# BLUETOOTH_UNIT.net
KiCad netlist of a schematic drawn in Altium Designer
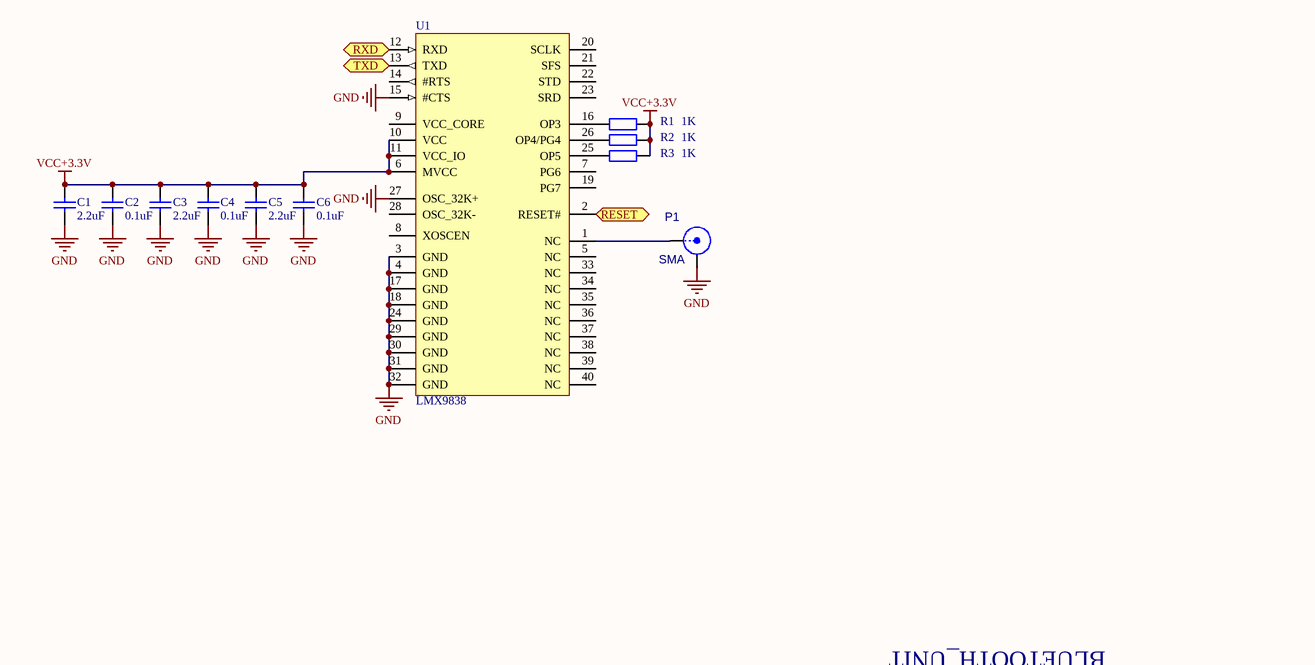
[diagram p0: BLUETOOTH_UNIT.SchDoc]

(export (version "E")
  (design (tool "Eeschema 10.0.6"))
  (components
    (comp (ref "C1")
      (value "2.2uF")
      (footprint "C0603")
      (description "Capasitor_SMD_0808/")
      (fields (field (name "Comment") "0805"))
      (libsource (lib "NEW") (part "Capasitor_SMD_0805"))
    )
    (comp (ref "C2")
      (value "0.1uF")
      (footprint "C0603")
      (description "Capasitor_SMD_0808/")
      (fields (field (name "Comment") "0805"))
      (libsource (lib "NEW") (part "Capasitor_SMD_0805"))
    )
    (comp (ref "C3")
      (value "2.2uF")
      (footprint "C0603")
      (description "Capasitor_SMD_0808/")
      (fields (field (name "Comment") "0805"))
      (libsource (lib "NEW") (part "Capasitor_SMD_0805"))
    )
    (comp (ref "C4")
      (value "0.1uF")
      (footprint "C0603")
      (description "Capasitor_SMD_0808/")
      (fields (field (name "Comment") "0805"))
      (libsource (lib "NEW") (part "Capasitor_SMD_0805"))
    )
    (comp (ref "C5")
      (value "2.2uF")
      (footprint "C0603")
      (description "Capasitor_SMD_0808/")
      (fields (field (name "Comment") "0805"))
      (libsource (lib "NEW") (part "Capasitor_SMD_0805"))
    )
    (comp (ref "C6")
      (value "0.1uF")
      (footprint "C0603")
      (description "Capasitor_SMD_0808/")
      (fields (field (name "Comment") "0805"))
      (libsource (lib "NEW") (part "Capasitor_SMD_0805"))
    )
    (comp (ref "P1")
      (value "SMA")
      (footprint "SMA")
      (fields (field (name "PUBLISHER") "Altium Limited"))
      (libsource (lib "NEW") (part "SMA"))
    )
    (comp (ref "R1")
      (value "1K")
      (footprint "C0603")
      (description "Resistor")
      (fields (field (name "Comment") "RES"))
      (libsource (lib "NEW") (part "RES"))
    )
    (comp (ref "R2")
      (value "1K")
      (footprint "C0603")
      (description "Resistor")
      (fields (field (name "Comment") "RES"))
      (libsource (lib "NEW") (part "RES"))
    )
    (comp (ref "R3")
      (value "1K")
      (footprint "C0603")
      (description "Resistor")
      (fields (field (name "Comment") "RES"))
      (libsource (lib "NEW") (part "RES"))
    )
    (comp (ref "U1")
      (value "LMX9838")
      (footprint "LMX9838")
      (description "Bluetooth module")
      (libsource (lib "NEW") (part "LMX9838"))
    )
  )
  (nets
    (net (code "1") (name "/RESET") (class "Default")
      (node (ref "U1") (pin "2") (pinfunction "RESET#_2") (pintype "passive"))
    )
    (net (code "2") (name "/RXD") (class "Default")
      (node (ref "U1") (pin "12") (pinfunction "RXD_12") (pintype "input"))
    )
    (net (code "3") (name "/TXD") (class "Default")
      (node (ref "U1") (pin "13") (pinfunction "TXD_13") (pintype "output"))
    )
    (net (code "4") (name "GND") (class "Default")
      (node (ref "C1") (pin "2") (pinfunction "2_2") (pintype "passive"))
      (node (ref "C2") (pin "2") (pinfunction "2_2") (pintype "passive"))
      (node (ref "C3") (pin "2") (pinfunction "2_2") (pintype "passive"))
      (node (ref "C4") (pin "2") (pinfunction "2_2") (pintype "passive"))
      (node (ref "C5") (pin "2") (pinfunction "2_2") (pintype "passive"))
      (node (ref "C6") (pin "2") (pinfunction "2_2") (pintype "passive"))
      (node (ref "P1") (pin "2") (pinfunction "Y_2") (pintype "passive"))
      (node (ref "U1") (pin "15") (pinfunction "#CTS_15") (pintype "input"))
      (node (ref "U1") (pin "17") (pinfunction "GND_17") (pintype "passive"))
      (node (ref "U1") (pin "18") (pinfunction "GND_18") (pintype "passive"))
      (node (ref "U1") (pin "24") (pinfunction "GND_24") (pintype "passive"))
      (node (ref "U1") (pin "27") (pinfunction "OSC_32K+_27") (pintype "passive"))
      (node (ref "U1") (pin "29") (pinfunction "GND_29") (pintype "passive"))
      (node (ref "U1") (pin "3") (pinfunction "GND_3") (pintype "passive"))
      (node (ref "U1") (pin "30") (pinfunction "GND_30") (pintype "passive"))
      (node (ref "U1") (pin "31") (pinfunction "GND_31") (pintype "passive"))
      (node (ref "U1") (pin "32") (pinfunction "GND_32") (pintype "passive"))
      (node (ref "U1") (pin "4") (pinfunction "GND_4") (pintype "passive"))
    )
    (net (code "5") (name "Net-(P1-X)") (class "Default")
      (node (ref "P1") (pin "1") (pinfunction "X_1") (pintype "passive"))
      (node (ref "U1") (pin "1") (pinfunction "NC_1") (pintype "passive"))
    )
    (net (code "6") (name "Net-(U1-OP3)") (class "Default")
      (node (ref "R1") (pin "1") (pinfunction "1_1") (pintype "passive"))
      (node (ref "U1") (pin "16") (pinfunction "OP3_16") (pintype "passive"))
    )
    (net (code "7") (name "Net-(U1-OP4{slash}PG4)") (class "Default")
      (node (ref "R2") (pin "1") (pinfunction "1_1") (pintype "passive"))
      (node (ref "U1") (pin "26") (pinfunction "OP4/PG4_26") (pintype "passive"))
    )
    (net (code "8") (name "Net-(U1-OP5)") (class "Default")
      (node (ref "R3") (pin "1") (pinfunction "1_1") (pintype "passive"))
      (node (ref "U1") (pin "25") (pinfunction "OP5_25") (pintype "passive"))
    )
    (net (code "9") (name "VCC+3.3V") (class "Default")
      (node (ref "C1") (pin "1") (pinfunction "1_1") (pintype "passive"))
      (node (ref "C2") (pin "1") (pinfunction "1_1") (pintype "passive"))
      (node (ref "C3") (pin "1") (pinfunction "1_1") (pintype "passive"))
      (node (ref "C4") (pin "1") (pinfunction "1_1") (pintype "passive"))
      (node (ref "C5") (pin "1") (pinfunction "1_1") (pintype "passive"))
      (node (ref "C6") (pin "1") (pinfunction "1_1") (pintype "passive"))
      (node (ref "R1") (pin "2") (pinfunction "2_2") (pintype "passive"))
      (node (ref "R2") (pin "2") (pinfunction "2_2") (pintype "passive"))
      (node (ref "R3") (pin "2") (pinfunction "2_2") (pintype "passive"))
      (node (ref "U1") (pin "10") (pinfunction "VCC_10") (pintype "passive"))
      (node (ref "U1") (pin "11") (pinfunction "VCC_IO_11") (pintype "passive"))
      (node (ref "U1") (pin "6") (pinfunction "MVCC_6") (pintype "passive"))
    )
    (net (code "10") (name "unconnected-(U1-#RTS-Pad14)") (class "Default")
      (node (ref "U1") (pin "14") (pinfunction "#RTS_14") (pintype "output"))
    )
    (net (code "11") (name "unconnected-(U1-NC-Pad5)") (class "Default")
      (node (ref "U1") (pin "5") (pinfunction "NC_5") (pintype "passive"))
    )
    (net (code "12") (name "unconnected-(U1-NC-Pad33)") (class "Default")
      (node (ref "U1") (pin "33") (pinfunction "NC_33") (pintype "passive"))
    )
    (net (code "13") (name "unconnected-(U1-NC-Pad34)") (class "Default")
      (node (ref "U1") (pin "34") (pinfunction "NC_34") (pintype "passive"))
    )
    (net (code "14") (name "unconnected-(U1-NC-Pad35)") (class "Default")
      (node (ref "U1") (pin "35") (pinfunction "NC_35") (pintype "passive"))
    )
    (net (code "15") (name "unconnected-(U1-NC-Pad36)") (class "Default")
      (node (ref "U1") (pin "36") (pinfunction "NC_36") (pintype "passive"))
    )
    (net (code "16") (name "unconnected-(U1-NC-Pad37)") (class "Default")
      (node (ref "U1") (pin "37") (pinfunction "NC_37") (pintype "passive"))
    )
    (net (code "17") (name "unconnected-(U1-NC-Pad38)") (class "Default")
      (node (ref "U1") (pin "38") (pinfunction "NC_38") (pintype "passive"))
    )
    (net (code "18") (name "unconnected-(U1-NC-Pad39)") (class "Default")
      (node (ref "U1") (pin "39") (pinfunction "NC_39") (pintype "passive"))
    )
    (net (code "19") (name "unconnected-(U1-NC-Pad40)") (class "Default")
      (node (ref "U1") (pin "40") (pinfunction "NC_40") (pintype "passive"))
    )
    (net (code "20") (name "unconnected-(U1-OSC_32K--Pad28)") (class "Default")
      (node (ref "U1") (pin "28") (pinfunction "OSC_32K-_28") (pintype "passive"))
    )
    (net (code "21") (name "unconnected-(U1-PG6-Pad7)") (class "Default")
      (node (ref "U1") (pin "7") (pinfunction "PG6_7") (pintype "passive"))
    )
    (net (code "22") (name "unconnected-(U1-PG7-Pad19)") (class "Default")
      (node (ref "U1") (pin "19") (pinfunction "PG7_19") (pintype "passive"))
    )
    (net (code "23") (name "unconnected-(U1-SCLK-Pad20)") (class "Default")
      (node (ref "U1") (pin "20") (pinfunction "SCLK_20") (pintype "passive"))
    )
    (net (code "24") (name "unconnected-(U1-SFS-Pad21)") (class "Default")
      (node (ref "U1") (pin "21") (pinfunction "SFS_21") (pintype "passive"))
    )
    (net (code "25") (name "unconnected-(U1-SRD-Pad23)") (class "Default")
      (node (ref "U1") (pin "23") (pinfunction "SRD_23") (pintype "passive"))
    )
    (net (code "26") (name "unconnected-(U1-STD-Pad22)") (class "Default")
      (node (ref "U1") (pin "22") (pinfunction "STD_22") (pintype "passive"))
    )
    (net (code "27") (name "unconnected-(U1-VCC_CORE-Pad9)") (class "Default")
      (node (ref "U1") (pin "9") (pinfunction "VCC_CORE_9") (pintype "passive"))
    )
    (net (code "28") (name "unconnected-(U1-XOSCEN-Pad8)") (class "Default")
      (node (ref "U1") (pin "8") (pinfunction "XOSCEN_8") (pintype "passive"))
    )
  )
)
